# tape-sensor.net
KiCad netlist of a schematic drawn in EAGLE
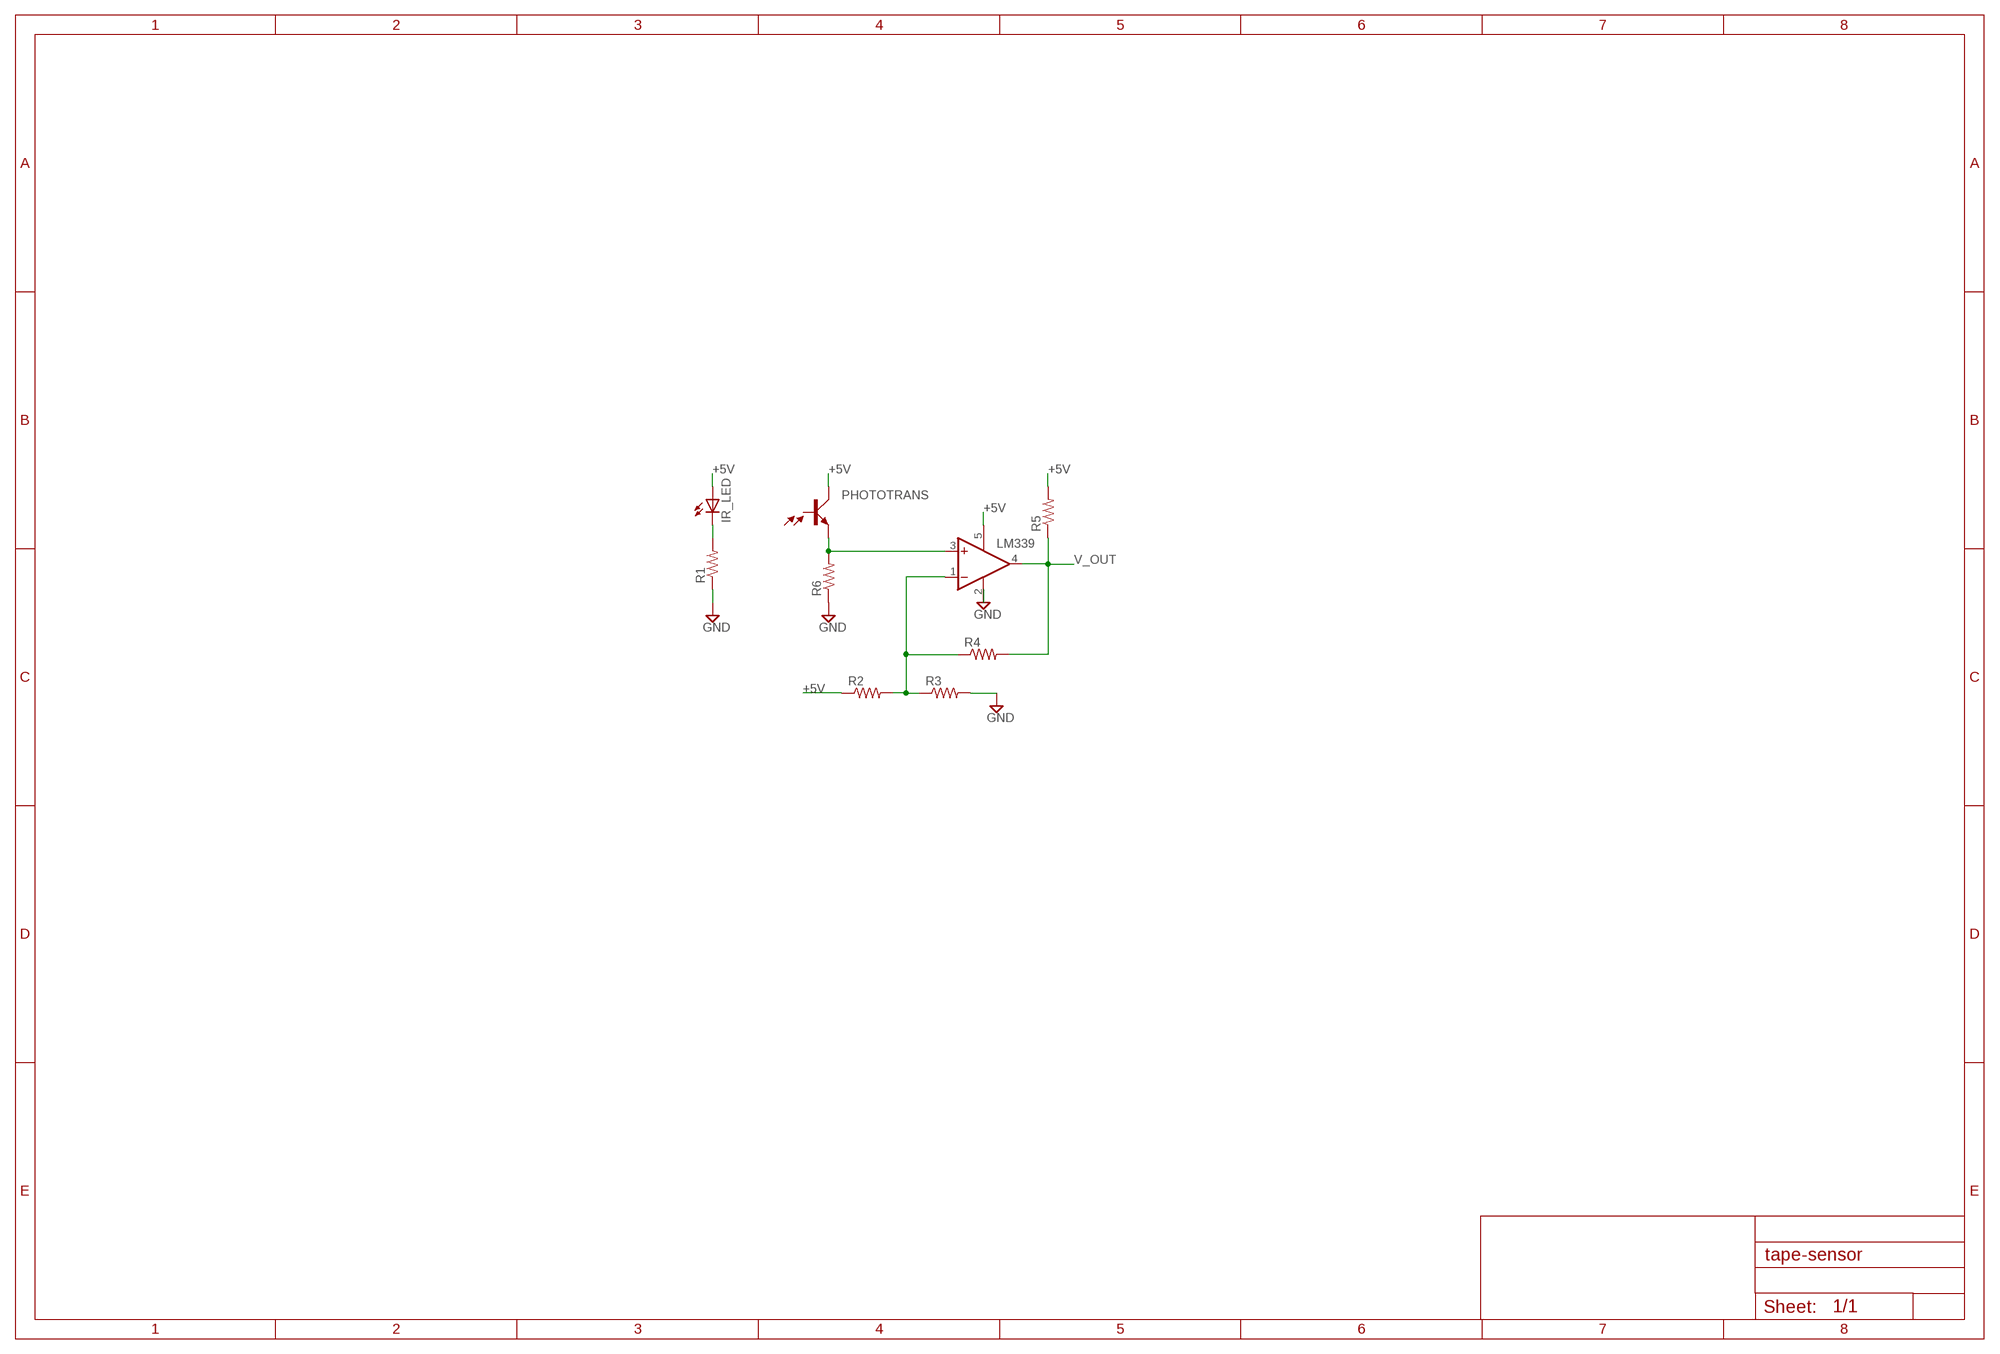
[diagram p0: schematic, sheet 1]

(export (version "E")
  (design (tool "Eeschema 10.0.6"))
  (components
    (comp (ref "IR_LED")
      (value "SFH482")
      (footprint "eagle-import:SFH482")
      (libsource (lib "eagle-import") (part "SFH482"))
    )
    (comp (ref "LM339")
      (value "TL331")
      (footprint "eagle-import:DBV-R-PDSO-G5")
      (libsource (lib "eagle-import") (part "TL331"))
    )
    (comp (ref "PHOTOTRANS")
      (value "SFH303")
      (footprint "eagle-import:SFH303")
      (libsource (lib "eagle-import") (part "SFH303"))
    )
    (comp (ref "R1")
      (value "R-US_0204/2V")
      (footprint "eagle-import:0204V")
      (libsource (lib "eagle-import") (part "R-US_0204/2V"))
    )
    (comp (ref "R2")
      (value "R-US_0204/2V")
      (footprint "eagle-import:0204V")
      (libsource (lib "eagle-import") (part "R-US_0204/2V"))
    )
    (comp (ref "R3")
      (value "R-US_0204/2V")
      (footprint "eagle-import:0204V")
      (libsource (lib "eagle-import") (part "R-US_0204/2V"))
    )
    (comp (ref "R4")
      (value "R-US_0204/2V")
      (footprint "eagle-import:0204V")
      (libsource (lib "eagle-import") (part "R-US_0204/2V"))
    )
    (comp (ref "R5")
      (value "R-US_0204/2V")
      (footprint "eagle-import:0204V")
      (libsource (lib "eagle-import") (part "R-US_0204/2V"))
    )
    (comp (ref "R6")
      (value "R-US_0204/2V")
      (footprint "eagle-import:0204V")
      (libsource (lib "eagle-import") (part "R-US_0204/2V"))
    )
  )
  (nets
    (net (code "1") (name "/+5V") (class "Default")
      (node (ref "IR_LED") (pin "A") (pinfunction "A_A") (pintype "passive"))
      (node (ref "LM339") (pin "5") (pinfunction "V+_5") (pintype "power_in"))
      (node (ref "PHOTOTRANS") (pin "2") (pinfunction "C_2") (pintype "passive"))
      (node (ref "R2") (pin "1") (pinfunction "1_1") (pintype "passive"))
      (node (ref "R5") (pin "2") (pinfunction "2_2") (pintype "passive"))
    )
    (net (code "2") (name "/V_OUT") (class "Default")
      (node (ref "LM339") (pin "4") (pinfunction "OUT_4") (pintype "output"))
      (node (ref "R4") (pin "2") (pinfunction "2_2") (pintype "passive"))
      (node (ref "R5") (pin "1") (pinfunction "1_1") (pintype "passive"))
    )
    (net (code "3") (name "GND") (class "Default")
      (node (ref "LM339") (pin "2") (pinfunction "GND_2") (pintype "power_in"))
      (node (ref "R1") (pin "1") (pinfunction "1_1") (pintype "passive"))
      (node (ref "R3") (pin "2") (pinfunction "2_2") (pintype "passive"))
      (node (ref "R6") (pin "1") (pinfunction "1_1") (pintype "passive"))
    )
    (net (code "4") (name "Net-(IR_LED-C)") (class "Default")
      (node (ref "IR_LED") (pin "K") (pinfunction "C_K") (pintype "passive"))
      (node (ref "R1") (pin "2") (pinfunction "2_2") (pintype "passive"))
    )
    (net (code "5") (name "Net-(LM339-+IN)") (class "Default")
      (node (ref "LM339") (pin "3") (pinfunction "+IN_3") (pintype "input"))
      (node (ref "PHOTOTRANS") (pin "1") (pinfunction "E_1") (pintype "passive"))
      (node (ref "R6") (pin "2") (pinfunction "2_2") (pintype "passive"))
    )
    (net (code "6") (name "Net-(LM339--IN)") (class "Default")
      (node (ref "LM339") (pin "1") (pinfunction "-IN_1") (pintype "input"))
      (node (ref "R2") (pin "2") (pinfunction "2_2") (pintype "passive"))
      (node (ref "R3") (pin "1") (pinfunction "1_1") (pintype "passive"))
      (node (ref "R4") (pin "1") (pinfunction "1_1") (pintype "passive"))
    )
    (net (code "7") (name "unconnected-(PHOTOTRANS-B-Pad3)") (class "Default")
      (node (ref "PHOTOTRANS") (pin "3") (pinfunction "B_3") (pintype "passive"))
    )
  )
)
